# SD-Card.net
KiCad netlist of a schematic drawn in Altium Designer
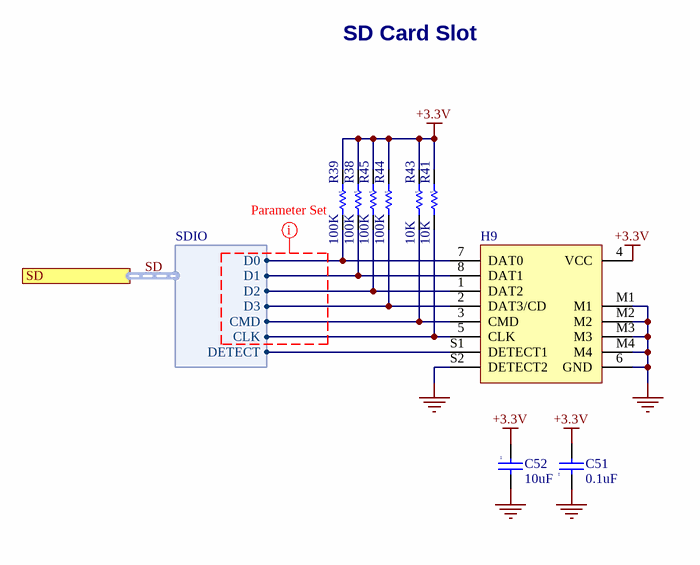
[diagram p0: SD-Card.SchDoc]

(export (version "E")
  (design (tool "Eeschema 10.0.6"))
  (components
    (comp (ref "C51")
      (value "0.1uF")
      (footprint "0402")
      (description "CAP CER .10UF 50V X7R 10% 0402")
      (fields
        (field (name "MANUFACTURER") "TDK Corporation")
        (field (name "MANUFACTURER PART NUMBER") "C1005X7R1H104K")
        (field (name "PUBLISHER") "Altium Limited")
      )
      (libsource (lib "") (part "Cap_1"))
    )
    (comp (ref "C52")
      (value "10uF")
      (footprint "0805")
      (description "CAP CER 10UF 35V X5R 0805")
      (fields
        (field (name "MANUFACTURER") "TDK")
        (field (name "MANUFACTURER PART NUMBER") "C2012X5R1V106K085AC")
        (field (name "PUBLISHER") "Altium Limited")
      )
      (libsource (lib "General") (part "Cap"))
    )
    (comp (ref "H9")
      (value "SD Card Socket")
      (footprint "114-00841-68")
      (description "CONN MICRO SD CARD PUSH-PULL R/A")
      (fields
        (field (name "MANUFACTURER") "Amphenol Commercial")
        (field (name "MANUFACTURER PART NUMBER") "114-00841-68")
      )
      (libsource (lib "Connectors") (part "SD Card Socket"))
    )
    (comp (ref "R38")
      (value "100K")
      (footprint "R0402")
      (description "RES SMD 100K OHM 1% 1/16W 0402")
      (fields
        (field (name "MANUFACTURER") "Panasonic")
        (field (name "MANUFACTURER PART NUMBER") "ERJ-2RKF1003X")
      )
      (libsource (lib "General") (part "Res"))
    )
    (comp (ref "R39")
      (value "100K")
      (footprint "R0402")
      (description "RES SMD 100K OHM 1% 1/16W 0402")
      (fields
        (field (name "MANUFACTURER") "Panasonic")
        (field (name "MANUFACTURER PART NUMBER") "ERJ-2RKF1003X")
      )
      (libsource (lib "General") (part "Res"))
    )
    (comp (ref "R41")
      (value "10K")
      (footprint "R0402")
      (description "RES 10K OHM 1/16W 1% 0402 SMD")
      (fields
        (field (name "MANUFACTURER") "Panasonic")
        (field (name "MANUFACTURER PART NUMBER") "ERJ-2RKF1002X")
      )
      (libsource (lib "General") (part "Res"))
    )
    (comp (ref "R43")
      (value "10K")
      (footprint "R0402")
      (description "RES 10K OHM 1/16W 1% 0402 SMD")
      (fields
        (field (name "MANUFACTURER") "Panasonic")
        (field (name "MANUFACTURER PART NUMBER") "ERJ-2RKF1002X")
      )
      (libsource (lib "General") (part "Res"))
    )
    (comp (ref "R44")
      (value "100K")
      (footprint "R0402")
      (description "RES SMD 100K OHM 1% 1/16W 0402")
      (fields
        (field (name "MANUFACTURER") "Panasonic")
        (field (name "MANUFACTURER PART NUMBER") "ERJ-2RKF1003X")
      )
      (libsource (lib "General") (part "Res"))
    )
    (comp (ref "R45")
      (value "100K")
      (footprint "R0402")
      (description "RES SMD 100K OHM 1% 1/16W 0402")
      (fields
        (field (name "MANUFACTURER") "Panasonic")
        (field (name "MANUFACTURER PART NUMBER") "ERJ-2RKF1003X")
      )
      (libsource (lib "General") (part "Res"))
    )
  )
  (nets
    (net (code "2") (name "+3.3V") (class "Default")
      (node (ref "C51") (pin "2") (pinfunction "2_2") (pintype "passive"))
      (node (ref "C52") (pin "1") (pinfunction "1_1") (pintype "passive"))
      (node (ref "H9") (pin "4") (pinfunction "VCC_4") (pintype "power_in"))
      (node (ref "R38") (pin "1") (pinfunction "1_1") (pintype "passive"))
      (node (ref "R39") (pin "1") (pinfunction "1_1") (pintype "passive"))
      (node (ref "R41") (pin "1") (pinfunction "1_1") (pintype "passive"))
      (node (ref "R43") (pin "1") (pinfunction "1_1") (pintype "passive"))
      (node (ref "R44") (pin "1") (pinfunction "1_1") (pintype "passive"))
      (node (ref "R45") (pin "1") (pinfunction "1_1") (pintype "passive"))
    )
    (net (code "3") (name "/CLK") (class "Default")
      (node (ref "H9") (pin "5") (pinfunction "CLK_5") (pintype "passive"))
      (node (ref "R41") (pin "2") (pinfunction "2_2") (pintype "passive"))
    )
    (net (code "4") (name "/CMD") (class "Default")
      (node (ref "H9") (pin "3") (pinfunction "CMD_3") (pintype "passive"))
      (node (ref "R43") (pin "2") (pinfunction "2_2") (pintype "passive"))
    )
    (net (code "5") (name "/D0") (class "Default")
      (node (ref "H9") (pin "7") (pinfunction "DAT0_7") (pintype "passive"))
      (node (ref "R39") (pin "2") (pinfunction "2_2") (pintype "passive"))
    )
    (net (code "6") (name "/D1") (class "Default")
      (node (ref "H9") (pin "8") (pinfunction "DAT1_8") (pintype "passive"))
      (node (ref "R38") (pin "2") (pinfunction "2_2") (pintype "passive"))
    )
    (net (code "7") (name "/D2") (class "Default")
      (node (ref "H9") (pin "1") (pinfunction "DAT2_1") (pintype "passive"))
      (node (ref "R45") (pin "2") (pinfunction "2_2") (pintype "passive"))
    )
    (net (code "8") (name "/D3") (class "Default")
      (node (ref "H9") (pin "2") (pinfunction "DAT3/CD_2") (pintype "passive"))
      (node (ref "R44") (pin "2") (pinfunction "2_2") (pintype "passive"))
    )
    (net (code "9") (name "/DETECT") (class "Default")
      (node (ref "H9") (pin "S1") (pinfunction "DETECT1_S1") (pintype "power_in"))
    )
    (net (code "11") (name "GND") (class "Default")
      (node (ref "C51") (pin "1") (pinfunction "1_1") (pintype "passive"))
      (node (ref "C52") (pin "2") (pinfunction "2_2") (pintype "passive"))
      (node (ref "H9") (pin "6") (pinfunction "GND_6") (pintype "power_in"))
      (node (ref "H9") (pin "M1") (pinfunction "M1_M1") (pintype "power_in"))
      (node (ref "H9") (pin "M2") (pinfunction "M2_M2") (pintype "power_in"))
      (node (ref "H9") (pin "M3") (pinfunction "M3_M3") (pintype "power_in"))
      (node (ref "H9") (pin "M4") (pinfunction "M4_M4") (pintype "power_in"))
      (node (ref "H9") (pin "S2") (pinfunction "DETECT2_S2") (pintype "power_in"))
    )
  )
)
